# Snickerdoodle_FPGA_JA.net
KiCad netlist of a schematic drawn in Altium Designer
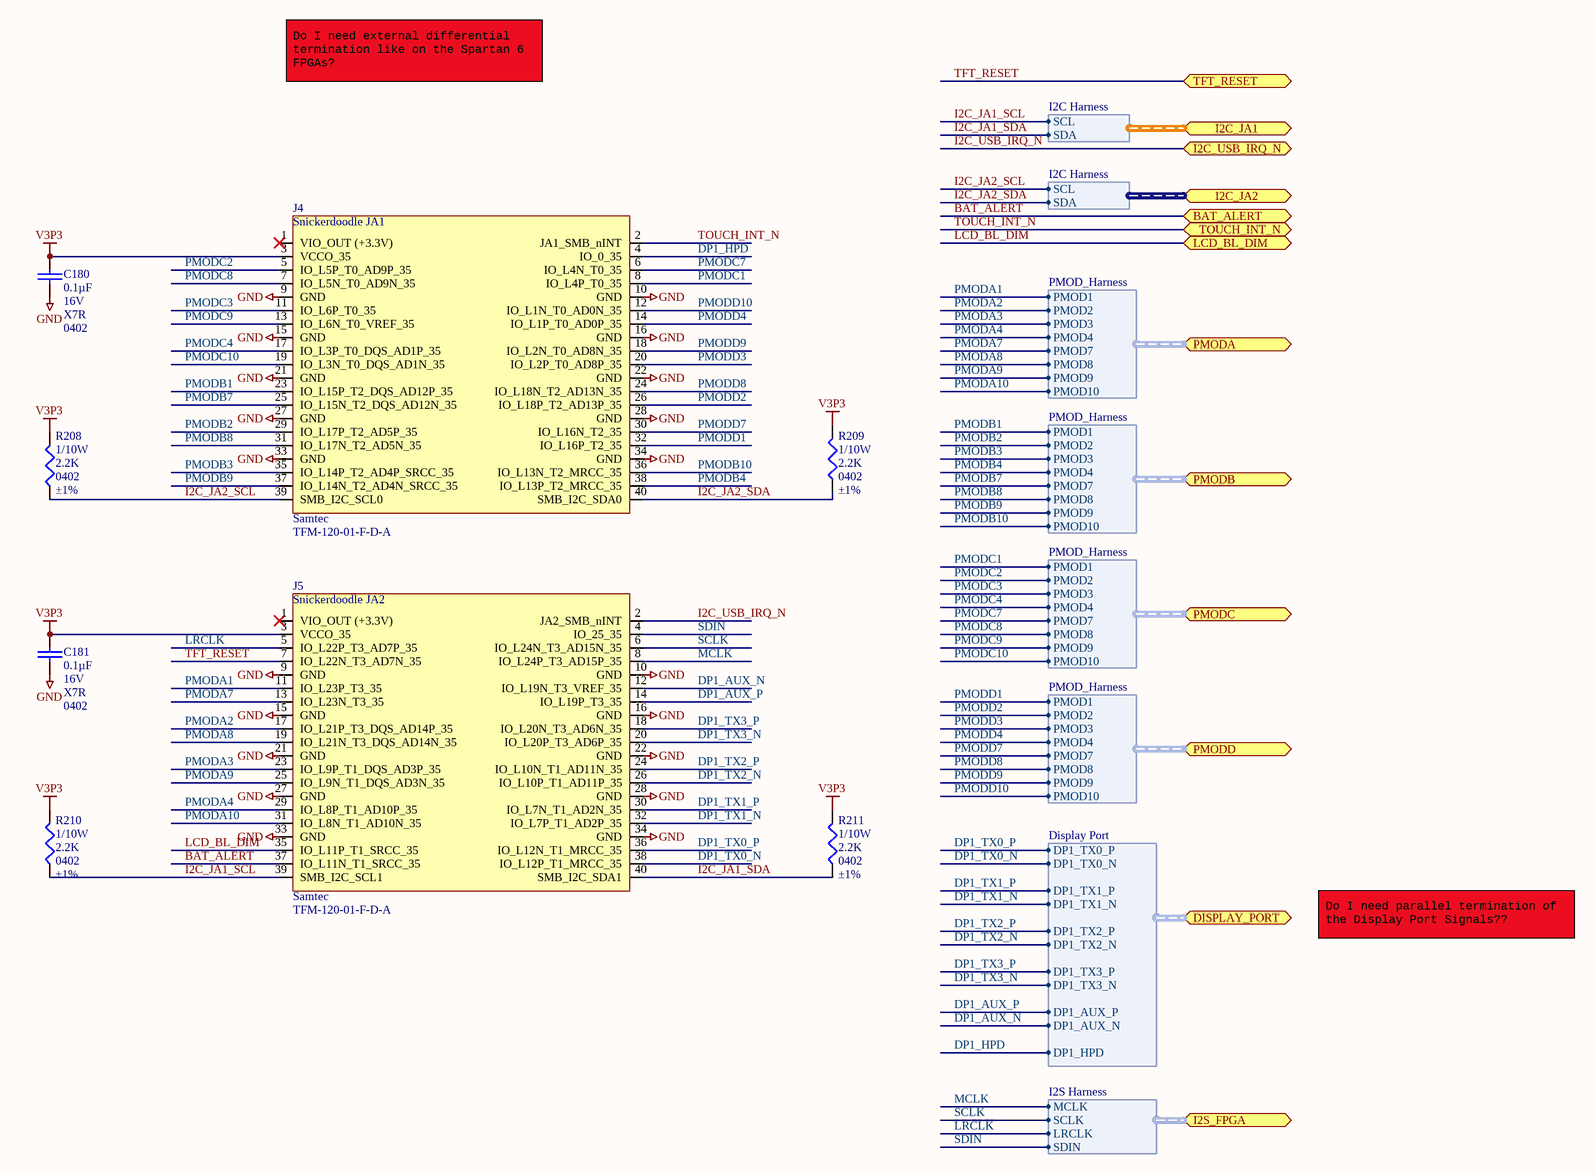
[diagram p0: Snickerdoodle FPGA JA.SchDoc]

(export (version "E")
  (design (tool "Eeschema 10.0.6"))
  (components
    (comp (ref "C180")
      (value "0.1uF")
      (footprint "C_0402")
      (description "CAP CER .10UF 16V X7R 0402")
      (fields
        (field (name "MANUFACTURER") "Murata Electronics North America")
        (field (name "MANUFACTURER PART NUMBER") "GRM155R71C104KA88J")
        (field (name "CAPACITANCE") "0.1µF")
        (field (name "VOLTAGE - RATED") "16V")
        (field (name "TEMPERATURE COEFFICIENT") "X7R")
        (field (name "PACKAGE / CASE") "0402")
      )
      (libsource (lib "Main LibraryX") (part "C_0402_0.1UF_16V"))
    )
    (comp (ref "C181")
      (value "0.1uF")
      (footprint "C_0402")
      (description "CAP CER .10UF 16V X7R 0402")
      (fields
        (field (name "MANUFACTURER") "Murata Electronics North America")
        (field (name "MANUFACTURER PART NUMBER") "GRM155R71C104KA88J")
        (field (name "CAPACITANCE") "0.1µF")
        (field (name "VOLTAGE - RATED") "16V")
        (field (name "TEMPERATURE COEFFICIENT") "X7R")
        (field (name "PACKAGE / CASE") "0402")
      )
      (libsource (lib "Main LibraryX") (part "C_0402_0.1UF_16V"))
    )
    (comp (ref "J4")
      (value "J_SNICKERDOODLE_JA1")
      (footprint "TFM12001-X-D-A")
      (description "SNICKERDOODLE JA1")
      (fields
        (field (name "MANUFACTURER") "Samtec")
        (field (name "MANUFACTURER PART NUMBER") "TFM-120-01-F-D-A")
      )
      (libsource (lib "Cospan Design") (part "J_SNICKERDOODLE_JA1"))
    )
    (comp (ref "J5")
      (value "J_SNICKERDOODLE_JA2")
      (footprint "TFM12001-X-D-A")
      (description "SNICKERDOODLE JA2")
      (fields
        (field (name "MANUFACTURER") "Samtec")
        (field (name "MANUFACTURER PART NUMBER") "TFM-120-01-F-D-A")
      )
      (libsource (lib "Cospan Design") (part "J_SNICKERDOODLE_JA2"))
    )
    (comp (ref "R208")
      (value "2.2k Ohms")
      (footprint "R_0402")
      (description "RES 2.20K OHM 1/10W 1% 0402 SMD")
      (fields
        (field (name "MANUFACTURER") "Yageo")
        (field (name "MANUFACTURER PART NUMBER") "RC0402FR-072K2L")
        (field (name "POWER (WATTS)") "1/10W")
        (field (name "RESISTANCE IN OHMS") "2.2K")
        (field (name "CASE") "0402")
        (field (name "TOLERANCE") "±1%")
      )
      (libsource (lib "Main Library") (part "R_0402_2.2K"))
    )
    (comp (ref "R209")
      (value "2.2k Ohms")
      (footprint "R_0402")
      (description "RES 2.20K OHM 1/10W 1% 0402 SMD")
      (fields
        (field (name "MANUFACTURER") "Yageo")
        (field (name "MANUFACTURER PART NUMBER") "RC0402FR-072K2L")
        (field (name "POWER (WATTS)") "1/10W")
        (field (name "RESISTANCE IN OHMS") "2.2K")
        (field (name "CASE") "0402")
        (field (name "TOLERANCE") "±1%")
      )
      (libsource (lib "Main Library") (part "R_0402_2.2K"))
    )
    (comp (ref "R210")
      (value "2.2k Ohms")
      (footprint "R_0402")
      (description "RES 2.20K OHM 1/10W 1% 0402 SMD")
      (fields
        (field (name "MANUFACTURER") "Yageo")
        (field (name "MANUFACTURER PART NUMBER") "RC0402FR-072K2L")
        (field (name "POWER (WATTS)") "1/10W")
        (field (name "RESISTANCE IN OHMS") "2.2K")
        (field (name "CASE") "0402")
        (field (name "TOLERANCE") "±1%")
      )
      (libsource (lib "Main Library") (part "R_0402_2.2K"))
    )
    (comp (ref "R211")
      (value "2.2k Ohms")
      (footprint "R_0402")
      (description "RES 2.20K OHM 1/10W 1% 0402 SMD")
      (fields
        (field (name "MANUFACTURER") "Yageo")
        (field (name "MANUFACTURER PART NUMBER") "RC0402FR-072K2L")
        (field (name "POWER (WATTS)") "1/10W")
        (field (name "RESISTANCE IN OHMS") "2.2K")
        (field (name "CASE") "0402")
        (field (name "TOLERANCE") "±1%")
      )
      (libsource (lib "Main Library") (part "R_0402_2.2K"))
    )
  )
  (nets
    (net (code "7") (name "/BAT_ALERT") (class "Default")
      (node (ref "J5") (pin "37") (pinfunction "IO_L11N_T1_SRCC_35_37") (pintype "passive"))
    )
    (net (code "8") (name "/DP1_AUX_N") (class "Default")
      (node (ref "J5") (pin "12") (pinfunction "IO_L19N_T3_VREF_35_12") (pintype "passive"))
    )
    (net (code "9") (name "/DP1_AUX_P") (class "Default")
      (node (ref "J5") (pin "14") (pinfunction "IO_L19P_T3_35_14") (pintype "passive"))
    )
    (net (code "10") (name "/DP1_HPD") (class "Default")
      (node (ref "J4") (pin "4") (pinfunction "IO_0_35_4") (pintype "passive"))
    )
    (net (code "11") (name "/DP1_TX0_N") (class "Default")
      (node (ref "J5") (pin "38") (pinfunction "IO_L12P_T1_MRCC_35_38") (pintype "passive"))
    )
    (net (code "12") (name "/DP1_TX0_P") (class "Default")
      (node (ref "J5") (pin "36") (pinfunction "IO_L12N_T1_MRCC_35_36") (pintype "passive"))
    )
    (net (code "13") (name "/DP1_TX1_N") (class "Default")
      (node (ref "J5") (pin "32") (pinfunction "IO_L7P_T1_AD2P_35_32") (pintype "passive"))
    )
    (net (code "14") (name "/DP1_TX1_P") (class "Default")
      (node (ref "J5") (pin "30") (pinfunction "IO_L7N_T1_AD2N_35_30") (pintype "passive"))
    )
    (net (code "15") (name "/DP1_TX2_N") (class "Default")
      (node (ref "J5") (pin "26") (pinfunction "IO_L10P_T1_AD11P_35_26") (pintype "passive"))
    )
    (net (code "16") (name "/DP1_TX2_P") (class "Default")
      (node (ref "J5") (pin "24") (pinfunction "IO_L10N_T1_AD11N_35_24") (pintype "passive"))
    )
    (net (code "17") (name "/DP1_TX3_N") (class "Default")
      (node (ref "J5") (pin "20") (pinfunction "IO_L20P_T3_AD6P_35_20") (pintype "passive"))
    )
    (net (code "18") (name "/DP1_TX3_P") (class "Default")
      (node (ref "J5") (pin "18") (pinfunction "IO_L20N_T3_AD6N_35_18") (pintype "passive"))
    )
    (net (code "19") (name "/I2C_JA1_SCL") (class "Default")
      (node (ref "J5") (pin "39") (pinfunction "SMB_I2C_SCL1_39") (pintype "passive"))
      (node (ref "R210") (pin "2") (pinfunction "2_2") (pintype "passive"))
    )
    (net (code "20") (name "/I2C_JA1_SDA") (class "Default")
      (node (ref "J5") (pin "40") (pinfunction "SMB_I2C_SDA1_40") (pintype "passive"))
      (node (ref "R211") (pin "2") (pinfunction "2_2") (pintype "passive"))
    )
    (net (code "21") (name "/I2C_JA2_SCL") (class "Default")
      (node (ref "J4") (pin "39") (pinfunction "SMB_I2C_SCL0_39") (pintype "passive"))
      (node (ref "R208") (pin "2") (pinfunction "2_2") (pintype "passive"))
    )
    (net (code "22") (name "/I2C_JA2_SDA") (class "Default")
      (node (ref "J4") (pin "40") (pinfunction "SMB_I2C_SDA0_40") (pintype "passive"))
      (node (ref "R209") (pin "2") (pinfunction "2_2") (pintype "passive"))
    )
    (net (code "23") (name "/I2C_USB_IRQ_N") (class "Default")
      (node (ref "J5") (pin "2") (pinfunction "JA2_SMB_nINT_2") (pintype "passive"))
    )
    (net (code "24") (name "/LCD_BL_DIM") (class "Default")
      (node (ref "J5") (pin "35") (pinfunction "IO_L11P_T1_SRCC_35_35") (pintype "passive"))
    )
    (net (code "25") (name "/LRCLK") (class "Default")
      (node (ref "J5") (pin "5") (pinfunction "IO_L22P_T3_AD7P_35_5") (pintype "passive"))
    )
    (net (code "26") (name "/MCLK") (class "Default")
      (node (ref "J5") (pin "8") (pinfunction "IO_L24P_T3_AD15P_35_8") (pintype "passive"))
    )
    (net (code "27") (name "/PMODA1") (class "Default")
      (node (ref "J5") (pin "11") (pinfunction "IO_L23P_T3_35_11") (pintype "passive"))
    )
    (net (code "28") (name "/PMODA2") (class "Default")
      (node (ref "J5") (pin "17") (pinfunction "IO_L21P_T3_DQS_AD14P_35_17") (pintype "passive"))
    )
    (net (code "29") (name "/PMODA3") (class "Default")
      (node (ref "J5") (pin "23") (pinfunction "IO_L9P_T1_DQS_AD3P_35_23") (pintype "passive"))
    )
    (net (code "30") (name "/PMODA4") (class "Default")
      (node (ref "J5") (pin "29") (pinfunction "IO_L8P_T1_AD10P_35_29") (pintype "passive"))
    )
    (net (code "31") (name "/PMODA7") (class "Default")
      (node (ref "J5") (pin "13") (pinfunction "IO_L23N_T3_35_13") (pintype "passive"))
    )
    (net (code "32") (name "/PMODA8") (class "Default")
      (node (ref "J5") (pin "19") (pinfunction "IO_L21N_T3_DQS_AD14N_35_19") (pintype "passive"))
    )
    (net (code "33") (name "/PMODA9") (class "Default")
      (node (ref "J5") (pin "25") (pinfunction "IO_L9N_T1_DQS_AD3N_35_25") (pintype "passive"))
    )
    (net (code "34") (name "/PMODA10") (class "Default")
      (node (ref "J5") (pin "31") (pinfunction "IO_L8N_T1_AD10N_35_31") (pintype "passive"))
    )
    (net (code "35") (name "/PMODB1") (class "Default")
      (node (ref "J4") (pin "23") (pinfunction "IO_L15P_T2_DQS_AD12P_35_23") (pintype "passive"))
    )
    (net (code "36") (name "/PMODB2") (class "Default")
      (node (ref "J4") (pin "29") (pinfunction "IO_L17P_T2_AD5P_35_29") (pintype "passive"))
    )
    (net (code "37") (name "/PMODB3") (class "Default")
      (node (ref "J4") (pin "35") (pinfunction "IO_L14P_T2_AD4P_SRCC_35_35") (pintype "passive"))
    )
    (net (code "38") (name "/PMODB4") (class "Default")
      (node (ref "J4") (pin "38") (pinfunction "IO_L13P_T2_MRCC_35_38") (pintype "passive"))
    )
    (net (code "39") (name "/PMODB7") (class "Default")
      (node (ref "J4") (pin "25") (pinfunction "IO_L15N_T2_DQS_AD12N_35_25") (pintype "passive"))
    )
    (net (code "40") (name "/PMODB8") (class "Default")
      (node (ref "J4") (pin "31") (pinfunction "IO_L17N_T2_AD5N_35_31") (pintype "passive"))
    )
    (net (code "41") (name "/PMODB9") (class "Default")
      (node (ref "J4") (pin "37") (pinfunction "IO_L14N_T2_AD4N_SRCC_35_37") (pintype "passive"))
    )
    (net (code "42") (name "/PMODB10") (class "Default")
      (node (ref "J4") (pin "36") (pinfunction "IO_L13N_T2_MRCC_35_36") (pintype "passive"))
    )
    (net (code "43") (name "/PMODC1") (class "Default")
      (node (ref "J4") (pin "8") (pinfunction "IO_L4P_T0_35_8") (pintype "passive"))
    )
    (net (code "44") (name "/PMODC2") (class "Default")
      (node (ref "J4") (pin "5") (pinfunction "IO_L5P_T0_AD9P_35_5") (pintype "passive"))
    )
    (net (code "45") (name "/PMODC3") (class "Default")
      (node (ref "J4") (pin "11") (pinfunction "IO_L6P_T0_35_11") (pintype "passive"))
    )
    (net (code "46") (name "/PMODC4") (class "Default")
      (node (ref "J4") (pin "17") (pinfunction "IO_L3P_T0_DQS_AD1P_35_17") (pintype "passive"))
    )
    (net (code "47") (name "/PMODC7") (class "Default")
      (node (ref "J4") (pin "6") (pinfunction "IO_L4N_T0_35_6") (pintype "passive"))
    )
    (net (code "48") (name "/PMODC8") (class "Default")
      (node (ref "J4") (pin "7") (pinfunction "IO_L5N_T0_AD9N_35_7") (pintype "passive"))
    )
    (net (code "49") (name "/PMODC9") (class "Default")
      (node (ref "J4") (pin "13") (pinfunction "IO_L6N_T0_VREF_35_13") (pintype "passive"))
    )
    (net (code "50") (name "/PMODC10") (class "Default")
      (node (ref "J4") (pin "19") (pinfunction "IO_L3N_T0_DQS_AD1N_35_19") (pintype "passive"))
    )
    (net (code "51") (name "/PMODD1") (class "Default")
      (node (ref "J4") (pin "32") (pinfunction "IO_L16P_T2_35_32") (pintype "passive"))
    )
    (net (code "52") (name "/PMODD2") (class "Default")
      (node (ref "J4") (pin "26") (pinfunction "IO_L18P_T2_AD13P_35_26") (pintype "passive"))
    )
    (net (code "53") (name "/PMODD3") (class "Default")
      (node (ref "J4") (pin "20") (pinfunction "IO_L2P_T0_AD8P_35_20") (pintype "passive"))
    )
    (net (code "54") (name "/PMODD4") (class "Default")
      (node (ref "J4") (pin "14") (pinfunction "IO_L1P_T0_AD0P_35_14") (pintype "passive"))
    )
    (net (code "55") (name "/PMODD7") (class "Default")
      (node (ref "J4") (pin "30") (pinfunction "IO_L16N_T2_35_30") (pintype "passive"))
    )
    (net (code "56") (name "/PMODD8") (class "Default")
      (node (ref "J4") (pin "24") (pinfunction "IO_L18N_T2_AD13N_35_24") (pintype "passive"))
    )
    (net (code "57") (name "/PMODD9") (class "Default")
      (node (ref "J4") (pin "18") (pinfunction "IO_L2N_T0_AD8N_35_18") (pintype "passive"))
    )
    (net (code "58") (name "/PMODD10") (class "Default")
      (node (ref "J4") (pin "12") (pinfunction "IO_L1N_T0_AD0N_35_12") (pintype "passive"))
    )
    (net (code "59") (name "/SCLK") (class "Default")
      (node (ref "J5") (pin "6") (pinfunction "IO_L24N_T3_AD15N_35_6") (pintype "passive"))
    )
    (net (code "60") (name "/SDIN") (class "Default")
      (node (ref "J5") (pin "4") (pinfunction "IO_25_35_4") (pintype "passive"))
    )
    (net (code "61") (name "/TFT_RESET") (class "Default")
      (node (ref "J5") (pin "7") (pinfunction "IO_L22N_T3_AD7N_35_7") (pintype "passive"))
    )
    (net (code "62") (name "/TOUCH_INT_N") (class "Default")
      (node (ref "J4") (pin "2") (pinfunction "JA1_SMB_nINT_2") (pintype "passive"))
    )
    (net (code "67") (name "GND") (class "Default")
      (node (ref "C180") (pin "1") (pinfunction "1_1") (pintype "passive"))
      (node (ref "C181") (pin "1") (pinfunction "1_1") (pintype "passive"))
      (node (ref "J4") (pin "10") (pinfunction "GND_10") (pintype "passive"))
      (node (ref "J4") (pin "15") (pinfunction "GND_15") (pintype "passive"))
      (node (ref "J4") (pin "16") (pinfunction "GND_16") (pintype "passive"))
      (node (ref "J4") (pin "21") (pinfunction "GND_21") (pintype "passive"))
      (node (ref "J4") (pin "22") (pinfunction "GND_22") (pintype "passive"))
      (node (ref "J4") (pin "27") (pinfunction "GND_27") (pintype "passive"))
      (node (ref "J4") (pin "28") (pinfunction "GND_28") (pintype "passive"))
      (node (ref "J4") (pin "33") (pinfunction "GND_33") (pintype "passive"))
      (node (ref "J4") (pin "34") (pinfunction "GND_34") (pintype "passive"))
      (node (ref "J4") (pin "9") (pinfunction "GND_9") (pintype "passive"))
      (node (ref "J5") (pin "10") (pinfunction "GND_10") (pintype "passive"))
      (node (ref "J5") (pin "15") (pinfunction "GND_15") (pintype "passive"))
      (node (ref "J5") (pin "16") (pinfunction "GND_16") (pintype "passive"))
      (node (ref "J5") (pin "21") (pinfunction "GND_21") (pintype "passive"))
      (node (ref "J5") (pin "22") (pinfunction "GND_22") (pintype "passive"))
      (node (ref "J5") (pin "27") (pinfunction "GND_27") (pintype "passive"))
      (node (ref "J5") (pin "28") (pinfunction "GND_28") (pintype "passive"))
      (node (ref "J5") (pin "33") (pinfunction "GND_33") (pintype "passive"))
      (node (ref "J5") (pin "34") (pinfunction "GND_34") (pintype "passive"))
      (node (ref "J5") (pin "9") (pinfunction "GND_9") (pintype "passive"))
    )
    (net (code "68") (name "V3P3") (class "Default")
      (node (ref "C180") (pin "2") (pinfunction "2_2") (pintype "passive"))
      (node (ref "C181") (pin "2") (pinfunction "2_2") (pintype "passive"))
      (node (ref "J4") (pin "3") (pinfunction "VCCO_35_3") (pintype "passive"))
      (node (ref "J5") (pin "3") (pinfunction "VCCO_35_3") (pintype "passive"))
      (node (ref "R208") (pin "1") (pinfunction "1_1") (pintype "passive"))
      (node (ref "R209") (pin "1") (pinfunction "1_1") (pintype "passive"))
      (node (ref "R210") (pin "1") (pinfunction "1_1") (pintype "passive"))
      (node (ref "R211") (pin "1") (pinfunction "1_1") (pintype "passive"))
    )
    (net (code "69") (name "unconnected-(J4-VIO_OUT_(+3.3V)-Pad1)") (class "Default")
      (node (ref "J4") (pin "1") (pinfunction "VIO_OUT_(+3.3V)_1") (pintype "passive+no_connect"))
    )
    (net (code "70") (name "unconnected-(J5-VIO_OUT_(+3.3V)-Pad1)") (class "Default")
      (node (ref "J5") (pin "1") (pinfunction "VIO_OUT_(+3.3V)_1") (pintype "passive+no_connect"))
    )
  )
)
